# Sheet_DRV8302_Driver.net
KiCad netlist of a schematic drawn in Altium Designer
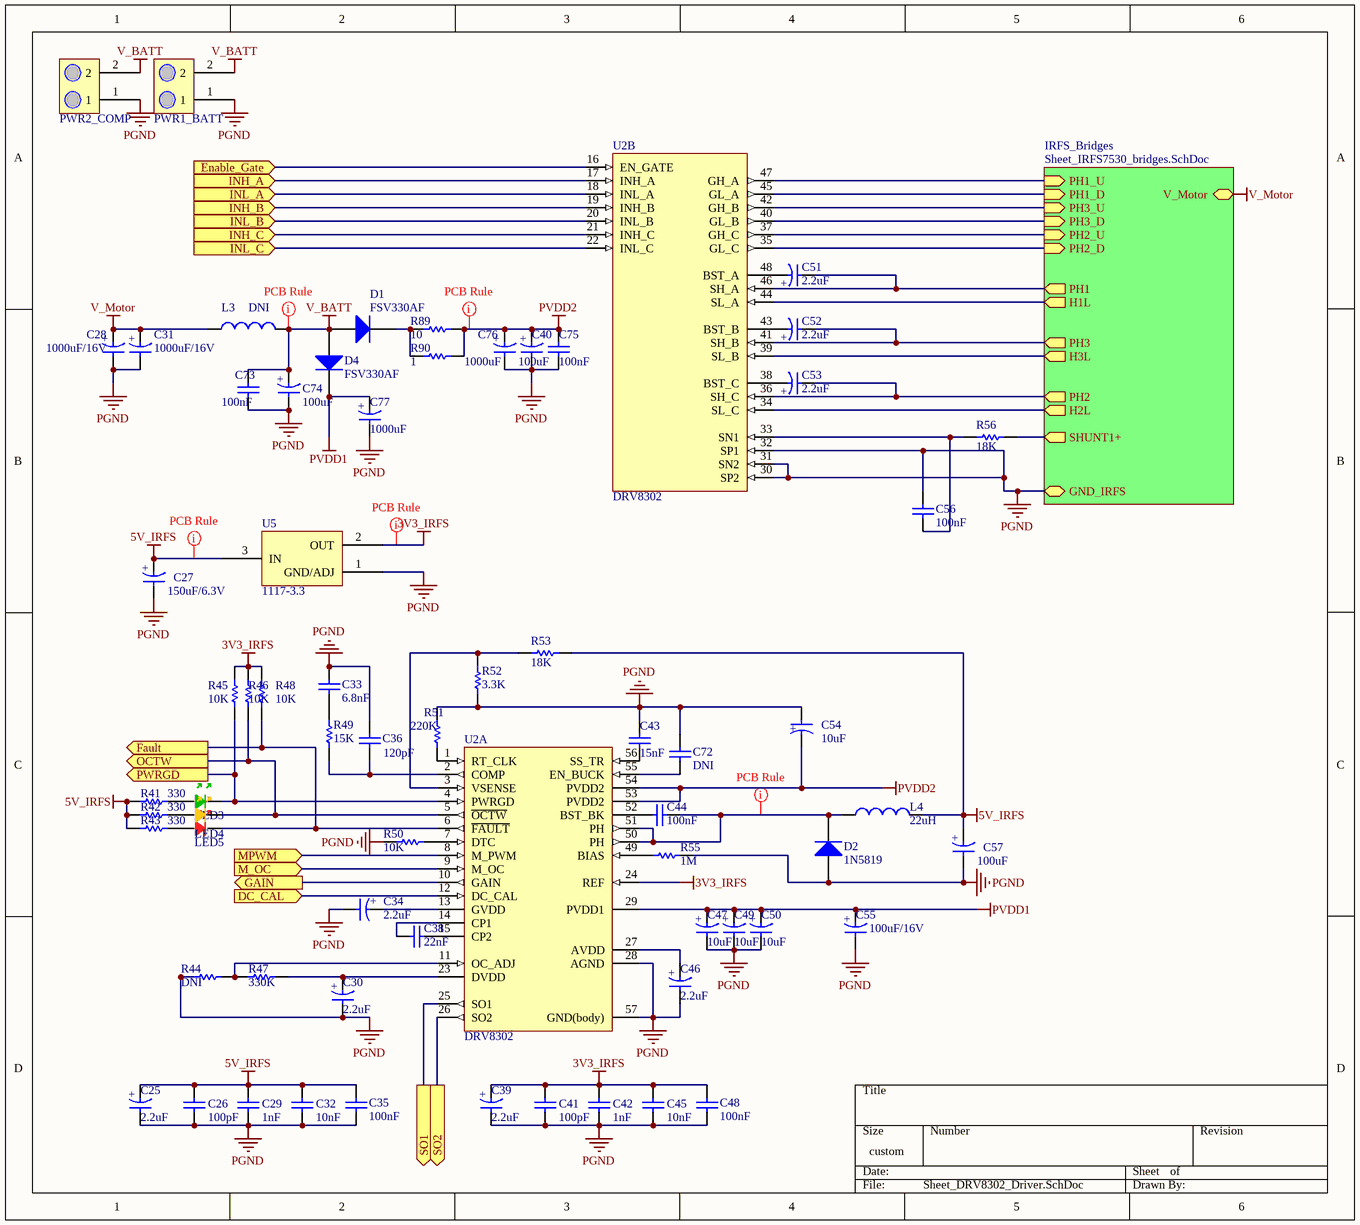
[diagram p0: Sheet_DRV8302_Driver.SchDoc]

(export (version "E")
  (design (tool "Eeschema 10.0.6"))
  (components
    (comp (ref "C25")
      (value "2.2uF")
      (footprint "ARPG_PCB_LIB:1608[0603] - Polar")
      (description "Capacitor")
      (libsource (lib "ARPG_PCB_LIB") (part "Cap_E"))
    )
    (comp (ref "C26")
      (value "100pF")
      (footprint "ARPG_PCB_LIB:1608[0603]")
      (description "Capacitor")
      (libsource (lib "AlmaLib1") (part "Cap_BP"))
    )
    (comp (ref "C27")
      (value "150uF/6.3V")
      (footprint "ARPG_PCB_LIB:6032 [2312]")
      (description "Capacitor")
      (libsource (lib "AlmaLib1") (part "Cap_E"))
    )
    (comp (ref "C28")
      (value "1000uF/16V")
      (footprint "ARPG_PCB_LIB:Large_SMD_Cap")
      (description "Capacitor")
      (libsource (lib "SchLib1") (part "Cap_E"))
    )
    (comp (ref "C29")
      (value "1nF")
      (footprint "ARPG_PCB_LIB:1608[0603]")
      (description "Capacitor")
      (libsource (lib "AlmaLib1") (part "Cap_BP"))
    )
    (comp (ref "C30")
      (value "2.2uF")
      (footprint "ARPG_PCB_LIB:1608[0603] - Polar")
      (description "Capacitor")
      (libsource (lib "ARPG_PCB_LIB") (part "Cap_E"))
    )
    (comp (ref "C31")
      (value "1000uF/16V")
      (footprint "ARPG_PCB_LIB:Large_SMD_Cap")
      (description "Capacitor")
      (libsource (lib "SchLib1") (part "Cap_E"))
    )
    (comp (ref "C32")
      (value "10nF")
      (footprint "ARPG_PCB_LIB:1608[0603]")
      (description "Capacitor")
      (libsource (lib "AlmaLib1") (part "Cap_BP"))
    )
    (comp (ref "C33")
      (value "6.8nF")
      (footprint "ARPG_PCB_LIB:1608[0603]")
      (description "Capacitor")
      (libsource (lib "AlmaLib1") (part "Cap_BP"))
    )
    (comp (ref "C34")
      (value "2.2uF")
      (footprint "ARPG_PCB_LIB:1608[0603] - Polar")
      (description "Capacitor")
      (libsource (lib "") (part "Cap_E_1"))
    )
    (comp (ref "C35")
      (value "100nF")
      (footprint "ARPG_PCB_LIB:1608[0603]")
      (description "Capacitor")
      (libsource (lib "AlmaLib1") (part "Cap_BP"))
    )
    (comp (ref "C36")
      (value "120pF")
      (footprint "ARPG_PCB_LIB:1608[0603]")
      (description "Capacitor")
      (libsource (lib "AlmaLib1") (part "Cap_BP"))
    )
    (comp (ref "C38")
      (value "22nF")
      (footprint "ARPG_PCB_LIB:1608[0603]")
      (description "Capacitor")
      (libsource (lib "AlmaLib1") (part "Cap_BP"))
    )
    (comp (ref "C39")
      (value "2.2uF")
      (footprint "ARPG_PCB_LIB:1608[0603] - Polar")
      (description "Capacitor")
      (libsource (lib "ARPG_PCB_LIB") (part "Cap_E"))
    )
    (comp (ref "C40")
      (value "100uF")
      (footprint "ARPG_PCB_LIB:6032 [2312]")
      (description "Capacitor")
      (libsource (lib "SchLib1") (part "Cap_E"))
    )
    (comp (ref "C41")
      (value "100pF")
      (footprint "ARPG_PCB_LIB:1608[0603]")
      (description "Capacitor")
      (libsource (lib "AlmaLib1") (part "Cap_BP"))
    )
    (comp (ref "C42")
      (value "1nF")
      (footprint "ARPG_PCB_LIB:1608[0603]")
      (description "Capacitor")
      (libsource (lib "AlmaLib1") (part "Cap_BP"))
    )
    (comp (ref "C43")
      (value "15nF")
      (footprint "ARPG_PCB_LIB:1608[0603]")
      (description "Capacitor")
      (libsource (lib "AlmaLib1") (part "Cap_BP"))
    )
    (comp (ref "C44")
      (value "100nF")
      (footprint "ARPG_PCB_LIB:1608[0603]")
      (description "Capacitor")
      (libsource (lib "AlmaLib1") (part "Cap_BP"))
    )
    (comp (ref "C45")
      (value "10nF")
      (footprint "ARPG_PCB_LIB:1608[0603]")
      (description "Capacitor")
      (libsource (lib "AlmaLib1") (part "Cap_BP"))
    )
    (comp (ref "C46")
      (value "2.2uF")
      (footprint "ARPG_PCB_LIB:1608[0603] - Polar")
      (description "Capacitor")
      (libsource (lib "ARPG_PCB_LIB") (part "Cap_E"))
    )
    (comp (ref "C47")
      (value "10uF")
      (footprint "ARPG_PCB_LIB:6032 [2312]")
      (description "Capacitor")
      (libsource (lib "AlmaLib1") (part "Cap_E"))
    )
    (comp (ref "C48")
      (value "100nF")
      (footprint "ARPG_PCB_LIB:1608[0603]")
      (description "Capacitor")
      (libsource (lib "AlmaLib1") (part "Cap_BP"))
    )
    (comp (ref "C49")
      (value "10uF")
      (footprint "ARPG_PCB_LIB:6032 [2312]")
      (description "Capacitor")
      (libsource (lib "AlmaLib1") (part "Cap_E"))
    )
    (comp (ref "C50")
      (value "10uF")
      (footprint "ARPG_PCB_LIB:6032 [2312]")
      (description "Capacitor")
      (libsource (lib "AlmaLib1") (part "Cap_E"))
    )
    (comp (ref "C51")
      (value "2.2uF")
      (footprint "ARPG_PCB_LIB:1608[0603] - Polar")
      (description "Capacitor")
      (libsource (lib "") (part "Cap_E_1"))
    )
    (comp (ref "C52")
      (value "2.2uF")
      (footprint "ARPG_PCB_LIB:1608[0603] - Polar")
      (description "Capacitor")
      (libsource (lib "") (part "Cap_E_1"))
    )
    (comp (ref "C53")
      (value "2.2uF")
      (footprint "ARPG_PCB_LIB:1608[0603] - Polar")
      (description "Capacitor")
      (libsource (lib "") (part "Cap_E_1"))
    )
    (comp (ref "C54")
      (value "10uF")
      (footprint "ARPG_PCB_LIB:6032 [2312]")
      (description "Capacitor")
      (libsource (lib "") (part "Cap_E_1"))
    )
    (comp (ref "C55")
      (value "100uF/16V")
      (footprint "ARPG_PCB_LIB:6032 [2312]")
      (description "Capacitor")
      (libsource (lib "AlmaLib1") (part "Cap_E"))
    )
    (comp (ref "C56")
      (value "100nF")
      (footprint "ARPG_PCB_LIB:1608[0603]")
      (description "Capacitor")
      (libsource (lib "AlmaLib1") (part "Cap_BP"))
    )
    (comp (ref "C57")
      (value "100uF")
      (footprint "ARPG_PCB_LIB:6032 [2312]")
      (description "Capacitor")
      (libsource (lib "AlmaLib1") (part "Cap_E"))
    )
    (comp (ref "C72")
      (value "DNI")
      (footprint "ARPG_PCB_LIB:1608[0603]")
      (description "Capacitor")
      (fields (field (name "Comment") "1uF"))
      (libsource (lib "ARPG_PCB_LIB") (part "Cap_BP"))
    )
    (comp (ref "C73")
      (value "100nF")
      (footprint "ARPG_PCB_LIB:1608[0603]")
      (description "Capacitor")
      (libsource (lib "AlmaLib1") (part "Cap_BP"))
    )
    (comp (ref "C74")
      (value "100uF")
      (footprint "ARPG_PCB_LIB:6032 [2312]")
      (description "Capacitor")
      (libsource (lib "SchLib1") (part "Cap_E"))
    )
    (comp (ref "C75")
      (value "100nF")
      (footprint "ARPG_PCB_LIB:1608[0603]")
      (description "Capacitor")
      (libsource (lib "AlmaLib1") (part "Cap_BP"))
    )
    (comp (ref "C76")
      (value "1000uF")
      (footprint "ARPG_PCB_LIB:Large_SMD_Cap")
      (description "Capacitor")
      (libsource (lib "SchLib1") (part "Cap_E"))
    )
    (comp (ref "C77")
      (value "1000uF")
      (footprint "ARPG_PCB_LIB:Large_SMD_Cap")
      (description "Capacitor")
      (libsource (lib "SchLib1") (part "Cap_E"))
    )
    (comp (ref "D1")
      (value "FSV330AF")
      (footprint "ARPG_PCB_LIB:FSV330AF/FSV340AF")
      (description "Diode")
      (libsource (lib "SchLib1") (part "Diode"))
    )
    (comp (ref "D2")
      (value "1N5819")
      (footprint "ARPG_PCB_LIB:DIODE-3")
      (description "Diode")
      (libsource (lib "SchLib1") (part "Diode"))
    )
    (comp (ref "D4")
      (value "FSV330AF")
      (footprint "ARPG_PCB_LIB:FSV330AF/FSV340AF")
      (description "Diode")
      (libsource (lib "SchLib1") (part "Diode"))
    )
    (comp (ref "L3")
      (value "DNI")
      (footprint "ARPG_PCB_LIB:Toroid")
      (description "Inductor")
      (libsource (lib "ARPG_PCB_LIB") (part "Inductor"))
    )
    (comp (ref "L4")
      (value "22uH")
      (footprint "ARPG_PCB_LIB:VLC2")
      (description "Inductor")
      (libsource (lib "AlmaLib1") (part "Inductor"))
    )
    (comp (ref "LED3")
      (value "LEDG")
      (footprint "ARPG_PCB_LIB:2012[0805]")
      (description "LED")
      (libsource (lib "AlmaLib1") (part "LED_G"))
    )
    (comp (ref "LED4")
      (value "LEDY")
      (footprint "ARPG_PCB_LIB:2012[0805]")
      (description "LED")
      (libsource (lib "AlmaLib1") (part "LED_Y"))
    )
    (comp (ref "LED5")
      (value "LEDR")
      (footprint "ARPG_PCB_LIB:2012[0805]")
      (description "LED")
      (libsource (lib "AlmaLib1") (part "LED_R"))
    )
    (comp (ref "PWR1_BATT")
      (value "Terminal2")
      (footprint "ARPG_PCB_LIB:TERM2")
      (description "Connector")
      (libsource (lib "SchLib1") (part "Terminal2"))
    )
    (comp (ref "PWR2_COMP")
      (value "Terminal2")
      (footprint "ARPG_PCB_LIB:TERM2")
      (description "Connector")
      (libsource (lib "SchLib1") (part "Terminal2"))
    )
    (comp (ref "R41")
      (value "330")
      (footprint "ARPG_PCB_LIB:1608[0603]")
      (description "Res")
      (libsource (lib "AlmaLib1") (part "Res"))
    )
    (comp (ref "R42")
      (value "330")
      (footprint "ARPG_PCB_LIB:1608[0603]")
      (description "Res")
      (libsource (lib "AlmaLib1") (part "Res"))
    )
    (comp (ref "R43")
      (value "330")
      (footprint "ARPG_PCB_LIB:1608[0603]")
      (description "Res")
      (libsource (lib "AlmaLib1") (part "Res"))
    )
    (comp (ref "R44")
      (value "DNI")
      (footprint "ARPG_PCB_LIB:1608[0603]")
      (description "Res")
      (libsource (lib "AlmaLib1") (part "Res"))
    )
    (comp (ref "R45")
      (value "10K")
      (footprint "ARPG_PCB_LIB:1608[0603]")
      (description "Res")
      (libsource (lib "AlmaLib1") (part "Res"))
    )
    (comp (ref "R46")
      (value "10K")
      (footprint "ARPG_PCB_LIB:1608[0603]")
      (description "Res")
      (libsource (lib "AlmaLib1") (part "Res"))
    )
    (comp (ref "R47")
      (value "330K")
      (footprint "ARPG_PCB_LIB:1608[0603]")
      (description "Res")
      (libsource (lib "AlmaLib1") (part "Res"))
    )
    (comp (ref "R48")
      (value "10K")
      (footprint "ARPG_PCB_LIB:1608[0603]")
      (description "Res")
      (libsource (lib "AlmaLib1") (part "Res"))
    )
    (comp (ref "R49")
      (value "15K")
      (footprint "ARPG_PCB_LIB:1608[0603]")
      (description "Res")
      (libsource (lib "AlmaLib1") (part "Res"))
    )
    (comp (ref "R50")
      (value "10K")
      (footprint "ARPG_PCB_LIB:1608[0603]")
      (description "Res")
      (libsource (lib "AlmaLib1") (part "Res"))
    )
    (comp (ref "R51")
      (value "220K")
      (footprint "ARPG_PCB_LIB:1608[0603]")
      (description "Res")
      (libsource (lib "AlmaLib1") (part "Res"))
    )
    (comp (ref "R52")
      (value "3.3K")
      (footprint "ARPG_PCB_LIB:1608[0603]")
      (description "Res")
      (libsource (lib "AlmaLib1") (part "Res"))
    )
    (comp (ref "R53")
      (value "18K")
      (footprint "ARPG_PCB_LIB:1608[0603]")
      (description "Res")
      (libsource (lib "AlmaLib1") (part "Res"))
    )
    (comp (ref "R55")
      (value "1M")
      (footprint "ARPG_PCB_LIB:1608[0603]")
      (description "Res")
      (libsource (lib "AlmaLib1") (part "Res"))
    )
    (comp (ref "R56")
      (value "18K")
      (footprint "ARPG_PCB_LIB:1608[0603]")
      (description "Res")
      (libsource (lib "AlmaLib1") (part "Res"))
    )
    (comp (ref "R89")
      (value "10")
      (footprint "ARPG_PCB_LIB:1608[0603]")
      (description "Res")
      (libsource (lib "AlmaLib1") (part "Res"))
    )
    (comp (ref "R90")
      (value "1")
      (footprint "ARPG_PCB_LIB:2012[0805]")
      (description "Res")
      (libsource (lib "AlmaLib1") (part "Res"))
    )
    (comp (ref "U2")
      (value "DRV8302")
      (footprint "ARPG_PCB_LIB:DRV8302")
      (libsource (lib "AlmaLib1") (part "DRV8302"))
    )
    (comp (ref "U5")
      (value "1117-3.3")
      (footprint "ARPG_PCB_LIB:SOT-223")
      (description "3.3V Voltage Regulator")
      (libsource (lib "AlmaLib1") (part "1117-3.3V"))
    )
  )
  (nets
    (net (code "1") (name "/DC_CAL") (class "Default")
      (node (ref "U2") (pin "12") (pinfunction "DC_CAL_12") (pintype "input"))
    )
    (net (code "2") (name "/Enable_Gate") (class "Default")
      (node (ref "U2") (pin "16") (pinfunction "EN_GATE_16") (pintype "input"))
    )
    (net (code "3") (name "/Fault") (class "Default")
      (node (ref "LED5") (pin "2") (pinfunction "K_2") (pintype "passive"))
      (node (ref "R48") (pin "1") (pinfunction "1_1") (pintype "passive"))
      (node (ref "U2") (pin "6") (pinfunction "~{FAULT}_6") (pintype "output"))
    )
    (net (code "4") (name "/GAIN") (class "Default")
      (node (ref "U2") (pin "10") (pinfunction "GAIN_10") (pintype "output"))
    )
    (net (code "5") (name "/H1L") (class "Default")
      (node (ref "U2") (pin "44") (pinfunction "SL_A_44") (pintype "input"))
    )
    (net (code "6") (name "/H2L") (class "Default")
      (node (ref "U2") (pin "34") (pinfunction "SL_C_34") (pintype "input"))
    )
    (net (code "7") (name "/H3L") (class "Default")
      (node (ref "U2") (pin "39") (pinfunction "SL_B_39") (pintype "input"))
    )
    (net (code "8") (name "/INH_A") (class "Default")
      (node (ref "U2") (pin "17") (pinfunction "INH_A_17") (pintype "input"))
    )
    (net (code "9") (name "/INH_B") (class "Default")
      (node (ref "U2") (pin "19") (pinfunction "INH_B_19") (pintype "input"))
    )
    (net (code "10") (name "/INH_C") (class "Default")
      (node (ref "U2") (pin "21") (pinfunction "INH_C_21") (pintype "input"))
    )
    (net (code "11") (name "/INL_A") (class "Default")
      (node (ref "U2") (pin "18") (pinfunction "INL_A_18") (pintype "input"))
    )
    (net (code "12") (name "/INL_B") (class "Default")
      (node (ref "U2") (pin "20") (pinfunction "INL_B_20") (pintype "input"))
    )
    (net (code "13") (name "/INL_C") (class "Default")
      (node (ref "U2") (pin "22") (pinfunction "INL_C_22") (pintype "input"))
    )
    (net (code "14") (name "/MPWM") (class "Default")
      (node (ref "U2") (pin "8") (pinfunction "M_PWM_8") (pintype "input"))
    )
    (net (code "15") (name "/M_OC") (class "Default")
      (node (ref "U2") (pin "9") (pinfunction "M_OC_9") (pintype "input"))
    )
    (net (code "16") (name "/OCTW") (class "Default")
      (node (ref "LED4") (pin "2") (pinfunction "K_2") (pintype "passive"))
      (node (ref "R46") (pin "1") (pinfunction "1_1") (pintype "passive"))
      (node (ref "U2") (pin "5") (pinfunction "~{OCTW}_5") (pintype "output"))
    )
    (net (code "17") (name "/PH1") (class "Default")
      (node (ref "C51") (pin "1") (pinfunction "1_1") (pintype "passive"))
      (node (ref "U2") (pin "46") (pinfunction "SH_A_46") (pintype "input"))
    )
    (net (code "18") (name "/PH1_D") (class "Default")
      (node (ref "U2") (pin "45") (pinfunction "GL_A_45") (pintype "output"))
    )
    (net (code "19") (name "/PH1_U") (class "Default")
      (node (ref "U2") (pin "47") (pinfunction "GH_A_47") (pintype "output"))
    )
    (net (code "20") (name "/PH2") (class "Default")
      (node (ref "C53") (pin "1") (pinfunction "1_1") (pintype "passive"))
      (node (ref "U2") (pin "36") (pinfunction "SH_C_36") (pintype "input"))
    )
    (net (code "21") (name "/PH2_D") (class "Default")
      (node (ref "U2") (pin "35") (pinfunction "GL_C_35") (pintype "output"))
    )
    (net (code "22") (name "/PH2_U") (class "Default")
      (node (ref "U2") (pin "37") (pinfunction "GH_C_37") (pintype "output"))
    )
    (net (code "23") (name "/PH3") (class "Default")
      (node (ref "C52") (pin "1") (pinfunction "1_1") (pintype "passive"))
      (node (ref "U2") (pin "41") (pinfunction "SH_B_41") (pintype "input"))
    )
    (net (code "24") (name "/PH3_D") (class "Default")
      (node (ref "U2") (pin "40") (pinfunction "GL_B_40") (pintype "output"))
    )
    (net (code "25") (name "/PH3_U") (class "Default")
      (node (ref "U2") (pin "42") (pinfunction "GH_B_42") (pintype "output"))
    )
    (net (code "26") (name "/PWRGD") (class "Default")
      (node (ref "LED3") (pin "2") (pinfunction "K_2") (pintype "passive"))
      (node (ref "R45") (pin "1") (pinfunction "1_1") (pintype "passive"))
      (node (ref "U2") (pin "4") (pinfunction "PWRGD_4") (pintype "input"))
    )
    (net (code "27") (name "/SHUNT1+") (class "Default")
      (node (ref "R56") (pin "2") (pinfunction "2_2") (pintype "passive"))
    )
    (net (code "28") (name "/SO1") (class "Default")
      (node (ref "U2") (pin "25") (pinfunction "SO1_25") (pintype "output"))
    )
    (net (code "29") (name "/SO2") (class "Default")
      (node (ref "U2") (pin "26") (pinfunction "SO2_26") (pintype "output"))
    )
    (net (code "30") (name "3V3_IRFS") (class "Default")
      (node (ref "C39") (pin "2") (pinfunction "2_2") (pintype "passive"))
      (node (ref "C41") (pin "2") (pinfunction "2_2") (pintype "passive"))
      (node (ref "C42") (pin "2") (pinfunction "2_2") (pintype "passive"))
      (node (ref "C45") (pin "2") (pinfunction "2_2") (pintype "passive"))
      (node (ref "C48") (pin "1") (pinfunction "1_1") (pintype "passive"))
      (node (ref "R45") (pin "2") (pinfunction "2_2") (pintype "passive"))
      (node (ref "R46") (pin "2") (pinfunction "2_2") (pintype "passive"))
      (node (ref "R48") (pin "2") (pinfunction "2_2") (pintype "passive"))
      (node (ref "U2") (pin "24") (pinfunction "REF_24") (pintype "input"))
      (node (ref "U5") (pin "2") (pinfunction "OUT_2") (pintype "passive"))
    )
    (net (code "31") (name "5V_IRFS") (class "Default")
      (node (ref "C25") (pin "2") (pinfunction "2_2") (pintype "passive"))
      (node (ref "C26") (pin "2") (pinfunction "2_2") (pintype "passive"))
      (node (ref "C27") (pin "2") (pinfunction "2_2") (pintype "passive"))
      (node (ref "C29") (pin "2") (pinfunction "2_2") (pintype "passive"))
      (node (ref "C32") (pin "2") (pinfunction "2_2") (pintype "passive"))
      (node (ref "C35") (pin "1") (pinfunction "1_1") (pintype "passive"))
      (node (ref "C57") (pin "2") (pinfunction "2_2") (pintype "passive"))
      (node (ref "L4") (pin "2") (pinfunction "2_2") (pintype "passive"))
      (node (ref "R41") (pin "1") (pinfunction "1_1") (pintype "passive"))
      (node (ref "R42") (pin "1") (pinfunction "1_1") (pintype "passive"))
      (node (ref "R43") (pin "1") (pinfunction "1_1") (pintype "passive"))
      (node (ref "R53") (pin "2") (pinfunction "2_2") (pintype "passive"))
      (node (ref "U5") (pin "3") (pinfunction "IN_3") (pintype "passive"))
    )
    (net (code "32") (name "Net-(C33-Pad2)") (class "Default")
      (node (ref "C33") (pin "2") (pinfunction "2_2") (pintype "passive"))
      (node (ref "R49") (pin "2") (pinfunction "2_2") (pintype "passive"))
    )
    (net (code "33") (name "Net-(D1-K)") (class "Default")
      (node (ref "D1") (pin "2") (pinfunction "K_2") (pintype "passive"))
      (node (ref "R89") (pin "2") (pinfunction "2_2") (pintype "passive"))
      (node (ref "R90") (pin "2") (pinfunction "2_2") (pintype "passive"))
    )
    (net (code "34") (name "Net-(D2-K)") (class "Default")
      (node (ref "C44") (pin "2") (pinfunction "2_2") (pintype "passive"))
      (node (ref "D2") (pin "2") (pinfunction "K_2") (pintype "passive"))
      (node (ref "L4") (pin "1") (pinfunction "1_1") (pintype "passive"))
      (node (ref "U2") (pin "50") (pinfunction "PH_50") (pintype "output"))
      (node (ref "U2") (pin "51") (pinfunction "PH_51") (pintype "output"))
    )
    (net (code "35") (name "Net-(LED3-A)") (class "Default")
      (node (ref "LED3") (pin "1") (pinfunction "A_1") (pintype "passive"))
      (node (ref "R41") (pin "2") (pinfunction "2_2") (pintype "passive"))
    )
    (net (code "36") (name "Net-(LED4-A)") (class "Default")
      (node (ref "LED4") (pin "1") (pinfunction "A_1") (pintype "passive"))
      (node (ref "R42") (pin "2") (pinfunction "2_2") (pintype "passive"))
    )
    (net (code "37") (name "Net-(LED5-A)") (class "Default")
      (node (ref "LED5") (pin "1") (pinfunction "A_1") (pintype "passive"))
      (node (ref "R43") (pin "2") (pinfunction "2_2") (pintype "passive"))
    )
    (net (code "38") (name "Net-(U2A-AVDD)") (class "Default")
      (node (ref "C46") (pin "2") (pinfunction "2_2") (pintype "passive"))
      (node (ref "U2") (pin "27") (pinfunction "AVDD_27") (pintype "power_in"))
    )
    (net (code "39") (name "Net-(U2A-BIAS)") (class "Default")
      (node (ref "R55") (pin "1") (pinfunction "1_1") (pintype "passive"))
      (node (ref "U2") (pin "49") (pinfunction "BIAS_49") (pintype "input"))
    )
    (net (code "40") (name "Net-(U2A-BST_BK)") (class "Default")
      (node (ref "C44") (pin "1") (pinfunction "1_1") (pintype "passive"))
      (node (ref "U2") (pin "52") (pinfunction "BST_BK_52") (pintype "power_in"))
    )
    (net (code "41") (name "Net-(U2A-COMP)") (class "Default")
      (node (ref "C36") (pin "2") (pinfunction "2_2") (pintype "passive"))
      (node (ref "R49") (pin "1") (pinfunction "1_1") (pintype "passive"))
      (node (ref "U2") (pin "2") (pinfunction "COMP_2") (pintype "output"))
    )
    (net (code "42") (name "Net-(U2A-CP1)") (class "Default")
      (node (ref "C38") (pin "2") (pinfunction "2_2") (pintype "passive"))
      (node (ref "U2") (pin "14") (pinfunction "CP1_14") (pintype "power_in"))
    )
    (net (code "43") (name "Net-(U2A-CP2)") (class "Default")
      (node (ref "C38") (pin "1") (pinfunction "1_1") (pintype "passive"))
      (node (ref "U2") (pin "15") (pinfunction "CP2_15") (pintype "power_in"))
    )
    (net (code "44") (name "Net-(U2A-DTC)") (class "Default")
      (node (ref "R50") (pin "2") (pinfunction "2_2") (pintype "passive"))
      (node (ref "U2") (pin "7") (pinfunction "DTC_7") (pintype "input"))
    )
    (net (code "45") (name "Net-(U2A-DVDD)") (class "Default")
      (node (ref "C30") (pin "2") (pinfunction "2_2") (pintype "passive"))
      (node (ref "R47") (pin "2") (pinfunction "2_2") (pintype "passive"))
      (node (ref "U2") (pin "23") (pinfunction "DVDD_23") (pintype "power_in"))
    )
    (net (code "46") (name "Net-(U2A-EN_BUCK)") (class "Default")
      (node (ref "C72") (pin "1") (pinfunction "1_1") (pintype "passive"))
      (node (ref "U2") (pin "55") (pinfunction "EN_BUCK_55") (pintype "input"))
    )
    (net (code "47") (name "Net-(U2A-GVDD)") (class "Default")
      (node (ref "C34") (pin "2") (pinfunction "2_2") (pintype "passive"))
      (node (ref "U2") (pin "13") (pinfunction "GVDD_13") (pintype "power_in"))
    )
    (net (code "48") (name "Net-(U2A-OC_ADJ)") (class "Default")
      (node (ref "R44") (pin "2") (pinfunction "2_2") (pintype "passive"))
      (node (ref "R47") (pin "1") (pinfunction "1_1") (pintype "passive"))
      (node (ref "U2") (pin "11") (pinfunction "OC_ADJ_11") (pintype "input"))
    )
    (net (code "49") (name "Net-(U2A-RT_CLK)") (class "Default")
      (node (ref "R51") (pin "2") (pinfunction "2_2") (pintype "passive"))
      (node (ref "U2") (pin "1") (pinfunction "RT_CLK_1") (pintype "input"))
    )
    (net (code "50") (name "Net-(U2A-SS_TR)") (class "Default")
      (node (ref "C43") (pin "2") (pinfunction "2_2") (pintype "passive"))
      (node (ref "U2") (pin "56") (pinfunction "SS_TR_56") (pintype "input"))
    )
    (net (code "51") (name "Net-(U2A-VSENSE)") (class "Default")
      (node (ref "R52") (pin "1") (pinfunction "1_1") (pintype "passive"))
      (node (ref "R53") (pin "1") (pinfunction "1_1") (pintype "passive"))
      (node (ref "U2") (pin "3") (pinfunction "VSENSE_3") (pintype "input"))
    )
    (net (code "52") (name "Net-(U2B-BST_A)") (class "Default")
      (node (ref "C51") (pin "2") (pinfunction "2_2") (pintype "passive"))
      (node (ref "U2") (pin "48") (pinfunction "BST_A_48") (pintype "power_in"))
    )
    (net (code "53") (name "Net-(U2B-BST_B)") (class "Default")
      (node (ref "C52") (pin "2") (pinfunction "2_2") (pintype "passive"))
      (node (ref "U2") (pin "43") (pinfunction "BST_B_43") (pintype "power_in"))
    )
    (net (code "54") (name "Net-(U2B-BST_C)") (class "Default")
      (node (ref "C53") (pin "2") (pinfunction "2_2") (pintype "passive"))
      (node (ref "U2") (pin "38") (pinfunction "BST_C_38") (pintype "power_in"))
    )
    (net (code "55") (name "Net-(U2B-SN1)") (class "Default")
      (node (ref "C56") (pin "2") (pinfunction "2_2") (pintype "passive"))
      (node (ref "R56") (pin "1") (pinfunction "1_1") (pintype "passive"))
      (node (ref "U2") (pin "33") (pinfunction "SN1_33") (pintype "input"))
    )
    (net (code "56") (name "PGND") (class "Default")
      (node (ref "C25") (pin "1") (pinfunction "1_1") (pintype "passive"))
      (node (ref "C26") (pin "1") (pinfunction "1_1") (pintype "passive"))
      (node (ref "C27") (pin "1") (pinfunction "1_1") (pintype "passive"))
      (node (ref "C28") (pin "1") (pinfunction "1_1") (pintype "passive"))
      (node (ref "C29") (pin "1") (pinfunction "1_1") (pintype "passive"))
      (node (ref "C30") (pin "1") (pinfunction "1_1") (pintype "passive"))
      (node (ref "C31") (pin "1") (pinfunction "1_1") (pintype "passive"))
      (node (ref "C32") (pin "1") (pinfunction "1_1") (pintype "passive"))
      (node (ref "C33") (pin "1") (pinfunction "1_1") (pintype "passive"))
      (node (ref "C34") (pin "1") (pinfunction "1_1") (pintype "passive"))
      (node (ref "C35") (pin "2") (pinfunction "2_2") (pintype "passive"))
      (node (ref "C36") (pin "1") (pinfunction "1_1") (pintype "passive"))
      (node (ref "C39") (pin "1") (pinfunction "1_1") (pintype "passive"))
      (node (ref "C40") (pin "1") (pinfunction "1_1") (pintype "passive"))
      (node (ref "C41") (pin "1") (pinfunction "1_1") (pintype "passive"))
      (node (ref "C42") (pin "1") (pinfunction "1_1") (pintype "passive"))
      (node (ref "C43") (pin "1") (pinfunction "1_1") (pintype "passive"))
      (node (ref "C45") (pin "1") (pinfunction "1_1") (pintype "passive"))
      (node (ref "C46") (pin "1") (pinfunction "1_1") (pintype "passive"))
      (node (ref "C47") (pin "1") (pinfunction "1_1") (pintype "passive"))
      (node (ref "C48") (pin "2") (pinfunction "2_2") (pintype "passive"))
      (node (ref "C49") (pin "1") (pinfunction "1_1") (pintype "passive"))
      (node (ref "C50") (pin "1") (pinfunction "1_1") (pintype "passive"))
      (node (ref "C54") (pin "1") (pinfunction "1_1") (pintype "passive"))
      (node (ref "C55") (pin "1") (pinfunction "1_1") (pintype "passive"))
      (node (ref "C56") (pin "1") (pinfunction "1_1") (pintype "passive"))
      (node (ref "C57") (pin "1") (pinfunction "1_1") (pintype "passive"))
      (node (ref "C72") (pin "2") (pinfunction "2_2") (pintype "passive"))
      (node (ref "C73") (pin "2") (pinfunction "2_2") (pintype "passive"))
      (node (ref "C74") (pin "1") (pinfunction "1_1") (pintype "passive"))
      (node (ref "C75") (pin "2") (pinfunction "2_2") (pintype "passive"))
      (node (ref "C76") (pin "1") (pinfunction "1_1") (pintype "passive"))
      (node (ref "C77") (pin "1") (pinfunction "1_1") (pintype "passive"))
      (node (ref "D2") (pin "1") (pinfunction "A_1") (pintype "passive"))
      (node (ref "PWR1_BATT") (pin "1") (pinfunction "1_1") (pintype "passive"))
      (node (ref "PWR2_COMP") (pin "1") (pinfunction "1_1") (pintype "passive"))
      (node (ref "R44") (pin "1") (pinfunction "1_1") (pintype "passive"))
      (node (ref "R50") (pin "1") (pinfunction "1_1") (pintype "passive"))
      (node (ref "R51") (pin "1") (pinfunction "1_1") (pintype "passive"))
      (node (ref "R52") (pin "2") (pinfunction "2_2") (pintype "passive"))
      (node (ref "R55") (pin "2") (pinfunction "2_2") (pintype "passive"))
      (node (ref "U2") (pin "28") (pinfunction "AGND_28") (pintype "power_in"))
      (node (ref "U2") (pin "30") (pinfunction "SP2_30") (pintype "input"))
      (node (ref "U2") (pin "31") (pinfunction "SN2_31") (pintype "input"))
      (node (ref "U2") (pin "32") (pinfunction "SP1_32") (pintype "input"))
      (node (ref "U2") (pin "57") (pinfunction "GND(body)_57") (pintype "power_in"))
      (node (ref "U5") (pin "1") (pinfunction "GND/ADJ_1") (pintype "passive"))
    )
    (net (code "57") (name "PVDD1") (class "Default")
      (node (ref "C47") (pin "2") (pinfunction "2_2") (pintype "passive"))
      (node (ref "C49") (pin "2") (pinfunction "2_2") (pintype "passive"))
      (node (ref "C50") (pin "2") (pinfunction "2_2") (pintype "passive"))
      (node (ref "C55") (pin "2") (pinfunction "2_2") (pintype "passive"))
      (node (ref "C77") (pin "2") (pinfunction "2_2") (pintype "passive"))
      (node (ref "D4") (pin "2") (pinfunction "K_2") (pintype "passive"))
      (node (ref "U2") (pin "29") (pinfunction "PVDD1_29") (pintype "power_in"))
    )
    (net (code "58") (name "PVDD2") (class "Default")
      (node (ref "C40") (pin "2") (pinfunction "2_2") (pintype "passive"))
      (node (ref "C54") (pin "2") (pinfunction "2_2") (pintype "passive"))
      (node (ref "C75") (pin "1") (pinfunction "1_1") (pintype "passive"))
      (node (ref "C76") (pin "2") (pinfunction "2_2") (pintype "passive"))
      (node (ref "R89") (pin "1") (pinfunction "1_1") (pintype "passive"))
      (node (ref "R90") (pin "1") (pinfunction "1_1") (pintype "passive"))
      (node (ref "U2") (pin "53") (pinfunction "PVDD2_53") (pintype "power_in"))
      (node (ref "U2") (pin "54") (pinfunction "PVDD2_54") (pintype "power_in"))
    )
    (net (code "59") (name "V_BATT") (class "Default")
      (node (ref "C73") (pin "1") (pinfunction "1_1") (pintype "passive"))
      (node (ref "C74") (pin "2") (pinfunction "2_2") (pintype "passive"))
      (node (ref "D1") (pin "1") (pinfunction "A_1") (pintype "passive"))
      (node (ref "D4") (pin "1") (pinfunction "A_1") (pintype "passive"))
      (node (ref "L3") (pin "2") (pinfunction "2_2") (pintype "passive"))
      (node (ref "PWR1_BATT") (pin "2") (pinfunction "2_2") (pintype "passive"))
      (node (ref "PWR2_COMP") (pin "2") (pinfunction "2_2") (pintype "passive"))
    )
    (net (code "60") (name "V_Motor") (class "Default")
      (node (ref "C28") (pin "2") (pinfunction "2_2") (pintype "passive"))
      (node (ref "C31") (pin "2") (pinfunction "2_2") (pintype "passive"))
      (node (ref "L3") (pin "1") (pinfunction "1_1") (pintype "passive"))
    )
  )
)
